# relay_load.net
KiCad netlist of a schematic drawn in EAGLE
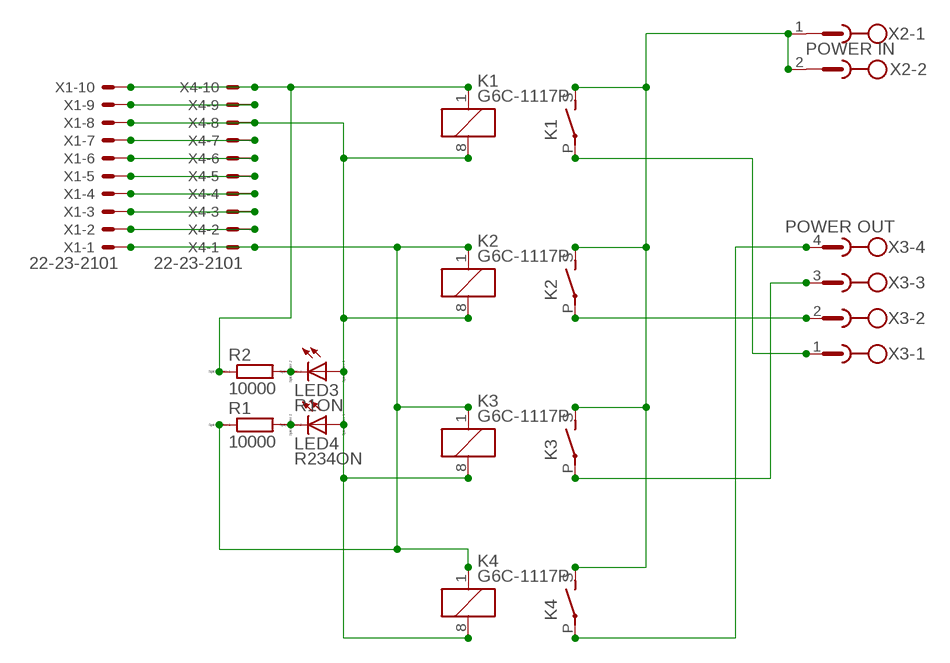
[diagram p0: schematic, sheet 1]

(export (version "E")
  (design (tool "Eeschema 10.0.6"))
  (components
    (comp (ref "K1")
      (value "G6C-1117P")
      (footprint "eagle-import:G6C-1117P")
      (libsource (lib "eagle-import") (part "G6C-1117P"))
    )
    (comp (ref "K2")
      (value "G6C-1117P")
      (footprint "eagle-import:G6C-1117P")
      (libsource (lib "eagle-import") (part "G6C-1117P"))
    )
    (comp (ref "K3")
      (value "G6C-1117P")
      (footprint "eagle-import:G6C-1117P")
      (libsource (lib "eagle-import") (part "G6C-1117P"))
    )
    (comp (ref "K4")
      (value "G6C-1117P")
      (footprint "eagle-import:G6C-1117P")
      (libsource (lib "eagle-import") (part "G6C-1117P"))
    )
    (comp (ref "LED3")
      (value "R1ON")
      (footprint "eagle-import:LED_1206")
      (libsource (lib "eagle-import") (part "LED_E"))
    )
    (comp (ref "LED4")
      (value "R234ON")
      (footprint "eagle-import:LED_1206")
      (libsource (lib "eagle-import") (part "LED_E"))
    )
    (comp (ref "R1")
      (value "10000")
      (footprint "eagle-import:R1206")
      (libsource (lib "eagle-import") (part "RR1206"))
    )
    (comp (ref "R2")
      (value "10000")
      (footprint "eagle-import:R1206")
      (libsource (lib "eagle-import") (part "RR1206"))
    )
    (comp (ref "X1")
      (value "22-23-2101")
      (footprint "eagle-import:22-23-2101")
      (fields (field (name "MF") "MOLEX"))
      (libsource (lib "eagle-import") (part "22-23-2101"))
    )
    (comp (ref "X2")
      (value "POWER IN")
      (footprint "eagle-import:MSTBV2")
      (libsource (lib "eagle-import") (part "MSTBV2"))
    )
    (comp (ref "X3")
      (value "POWER OUT")
      (footprint "eagle-import:MSTBV4")
      (fields (field (name "MPN") "MSTBV 2,5/4-GF-5.08"))
      (libsource (lib "eagle-import") (part "MSTBV4"))
    )
    (comp (ref "X4")
      (value "22-23-2101")
      (footprint "eagle-import:22-23-2101")
      (fields (field (name "MF") "MOLEX"))
      (libsource (lib "eagle-import") (part "22-23-2101"))
    )
  )
  (nets
    (net (code "1") (name "Net-(K1-PadP)") (class "Default")
      (node (ref "K1") (pin "P") (pinfunction "P_P") (pintype "passive"))
      (node (ref "X3") (pin "1") (pinfunction "1_1") (pintype "passive"))
    )
    (net (code "2") (name "Net-(K1A-2)") (class "Default")
      (node (ref "K1") (pin "8") (pinfunction "2_8") (pintype "passive"))
      (node (ref "K2") (pin "8") (pinfunction "2_8") (pintype "passive"))
      (node (ref "K3") (pin "8") (pinfunction "2_8") (pintype "passive"))
      (node (ref "K4") (pin "8") (pinfunction "2_8") (pintype "passive"))
      (node (ref "LED3") (pin "A") (pinfunction "A_A") (pintype "passive"))
      (node (ref "LED4") (pin "A") (pinfunction "A_A") (pintype "passive"))
      (node (ref "X1") (pin "8") (pinfunction "S_8") (pintype "passive"))
      (node (ref "X4") (pin "8") (pinfunction "S_8") (pintype "passive"))
    )
    (net (code "3") (name "Net-(LED3-PadC)") (class "Default")
      (node (ref "LED3") (pin "C") (pinfunction "C_C") (pintype "passive"))
      (node (ref "R2") (pin "2") (pinfunction "2_2") (pintype "passive"))
    )
    (net (code "4") (name "Net-(LED4-PadC)") (class "Default")
      (node (ref "LED4") (pin "C") (pinfunction "C_C") (pintype "passive"))
      (node (ref "R1") (pin "2") (pinfunction "2_2") (pintype "passive"))
    )
    (net (code "5") (name "Net-(X1A-S)") (class "Default")
      (node (ref "K2") (pin "1") (pinfunction "1_1") (pintype "passive"))
      (node (ref "K3") (pin "1") (pinfunction "1_1") (pintype "passive"))
      (node (ref "K4") (pin "1") (pinfunction "1_1") (pintype "passive"))
      (node (ref "R1") (pin "1") (pinfunction "1_1") (pintype "passive"))
      (node (ref "X1") (pin "1") (pinfunction "S_1") (pintype "passive"))
      (node (ref "X4") (pin "1") (pinfunction "S_1") (pintype "passive"))
    )
    (net (code "6") (name "Net-(X1B-S)") (class "Default")
      (node (ref "K1") (pin "1") (pinfunction "1_1") (pintype "passive"))
      (node (ref "R2") (pin "1") (pinfunction "1_1") (pintype "passive"))
      (node (ref "X1") (pin "10") (pinfunction "S_10") (pintype "passive"))
      (node (ref "X4") (pin "10") (pinfunction "S_10") (pintype "passive"))
    )
    (net (code "7") (name "Net-(X1C-S)") (class "Default")
      (node (ref "X1") (pin "2") (pinfunction "S_2") (pintype "passive"))
      (node (ref "X4") (pin "2") (pinfunction "S_2") (pintype "passive"))
    )
    (net (code "8") (name "Net-(X1D-S)") (class "Default")
      (node (ref "X1") (pin "3") (pinfunction "S_3") (pintype "passive"))
      (node (ref "X4") (pin "3") (pinfunction "S_3") (pintype "passive"))
    )
    (net (code "9") (name "Net-(X1E-S)") (class "Default")
      (node (ref "X1") (pin "4") (pinfunction "S_4") (pintype "passive"))
      (node (ref "X4") (pin "4") (pinfunction "S_4") (pintype "passive"))
    )
    (net (code "10") (name "Net-(X1F-S)") (class "Default")
      (node (ref "X1") (pin "5") (pinfunction "S_5") (pintype "passive"))
      (node (ref "X4") (pin "5") (pinfunction "S_5") (pintype "passive"))
    )
    (net (code "11") (name "Net-(X1G-S)") (class "Default")
      (node (ref "X1") (pin "6") (pinfunction "S_6") (pintype "passive"))
      (node (ref "X4") (pin "6") (pinfunction "S_6") (pintype "passive"))
    )
    (net (code "12") (name "Net-(X1H-S)") (class "Default")
      (node (ref "X1") (pin "7") (pinfunction "S_7") (pintype "passive"))
      (node (ref "X4") (pin "7") (pinfunction "S_7") (pintype "passive"))
    )
    (net (code "13") (name "Net-(X1J-S)") (class "Default")
      (node (ref "X1") (pin "9") (pinfunction "S_9") (pintype "passive"))
      (node (ref "X4") (pin "9") (pinfunction "S_9") (pintype "passive"))
    )
    (net (code "14") (name "Net-(X2A-SK)") (class "Default")
      (node (ref "K1") (pin "S") (pinfunction "S_S") (pintype "passive"))
      (node (ref "K2") (pin "S") (pinfunction "S_S") (pintype "passive"))
      (node (ref "K3") (pin "S") (pinfunction "S_S") (pintype "passive"))
      (node (ref "K4") (pin "S") (pinfunction "S_S") (pintype "passive"))
      (node (ref "X2") (pin "1") (pinfunction "SK_1") (pintype "passive"))
      (node (ref "X2") (pin "2") (pinfunction "SK_2") (pintype "passive"))
    )
    (net (code "15") (name "Net-(X3B-1)") (class "Default")
      (node (ref "K2") (pin "P") (pinfunction "P_P") (pintype "passive"))
      (node (ref "X3") (pin "2") (pinfunction "1_2") (pintype "passive"))
    )
    (net (code "16") (name "Net-(X3C-1)") (class "Default")
      (node (ref "K3") (pin "P") (pinfunction "P_P") (pintype "passive"))
      (node (ref "X3") (pin "3") (pinfunction "1_3") (pintype "passive"))
    )
    (net (code "17") (name "Net-(X3D-1)") (class "Default")
      (node (ref "K4") (pin "P") (pinfunction "P_P") (pintype "passive"))
      (node (ref "X3") (pin "4") (pinfunction "1_4") (pintype "passive"))
    )
  )
)
